# flash-interface.net
KiCad netlist of a schematic drawn in EAGLE
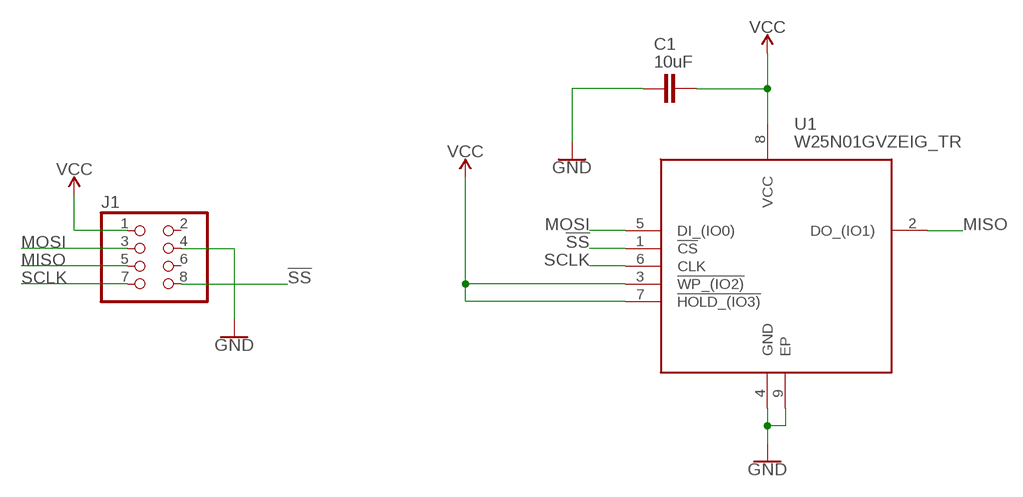
[diagram p0: schematic, sheet 1]

(export (version "E")
  (design (tool "Eeschema 10.0.6"))
  (components
    (comp (ref "C1")
      (value "10uF")
      (footprint "eagle-import:0805")
      (libsource (lib "eagle-import") (part "10UF-0805-10V-10%"))
    )
    (comp (ref "J1")
      (value "PINHD-2X4")
      (footprint "eagle-import:2X04")
      (libsource (lib "eagle-import") (part "PINHD-2X4"))
    )
    (comp (ref "U1")
      (value "W25N01GVZEIG_TR")
      (footprint "eagle-import:SON127P800X600X80-9N")
      (fields
        (field (name "MANUFACTURER_PART_NUMBER") "W25N01GVZEIG TR")
        (field (name "MOUSER_PART_NUMBER") "454-W25N01GVZEIGTR")
      )
      (libsource (lib "eagle-import") (part "W25N01GVZEIG_TR"))
    )
  )
  (nets
    (net (code "1") (name "/MISO") (class "Default")
      (node (ref "J1") (pin "5") (pinfunction "5_5") (pintype "passive"))
      (node (ref "U1") (pin "2") (pinfunction "DO_(IO1)_2") (pintype "bidirectional"))
    )
    (net (code "2") (name "/MOSI") (class "Default")
      (node (ref "J1") (pin "3") (pinfunction "3_3") (pintype "passive"))
      (node (ref "U1") (pin "5") (pinfunction "DI_(IO0)_5") (pintype "bidirectional"))
    )
    (net (code "3") (name "/SCLK") (class "Default")
      (node (ref "J1") (pin "7") (pinfunction "7_7") (pintype "passive"))
      (node (ref "U1") (pin "6") (pinfunction "CLK_6") (pintype "bidirectional"))
    )
    (net (code "4") (name "/~{SS}") (class "Default")
      (node (ref "J1") (pin "8") (pinfunction "8_8") (pintype "passive"))
      (node (ref "U1") (pin "1") (pinfunction "~{CS}_1") (pintype "bidirectional"))
    )
    (net (code "5") (name "GND") (class "Default")
      (node (ref "C1") (pin "2") (pinfunction "2_2") (pintype "passive"))
      (node (ref "J1") (pin "4") (pinfunction "4_4") (pintype "passive"))
      (node (ref "U1") (pin "4") (pinfunction "GND_4") (pintype "bidirectional"))
      (node (ref "U1") (pin "9") (pinfunction "EP_9") (pintype "bidirectional"))
    )
    (net (code "6") (name "VCC") (class "Default")
      (node (ref "C1") (pin "1") (pinfunction "1_1") (pintype "passive"))
      (node (ref "J1") (pin "1") (pinfunction "1_1") (pintype "passive"))
      (node (ref "U1") (pin "3") (pinfunction "~{WP_(IO2})_3") (pintype "bidirectional"))
      (node (ref "U1") (pin "7") (pinfunction "~{HOLD_(IO3})_7") (pintype "bidirectional"))
      (node (ref "U1") (pin "8") (pinfunction "VCC_8") (pintype "bidirectional"))
    )
    (net (code "7") (name "unconnected-(J1-Pad2)") (class "Default")
      (node (ref "J1") (pin "2") (pinfunction "2_2") (pintype "passive"))
    )
    (net (code "8") (name "unconnected-(J1-Pad6)") (class "Default")
      (node (ref "J1") (pin "6") (pinfunction "6_6") (pintype "passive"))
    )
  )
)
